# eeZee_big_tiny.net
KiCad netlist of a schematic drawn in EAGLE
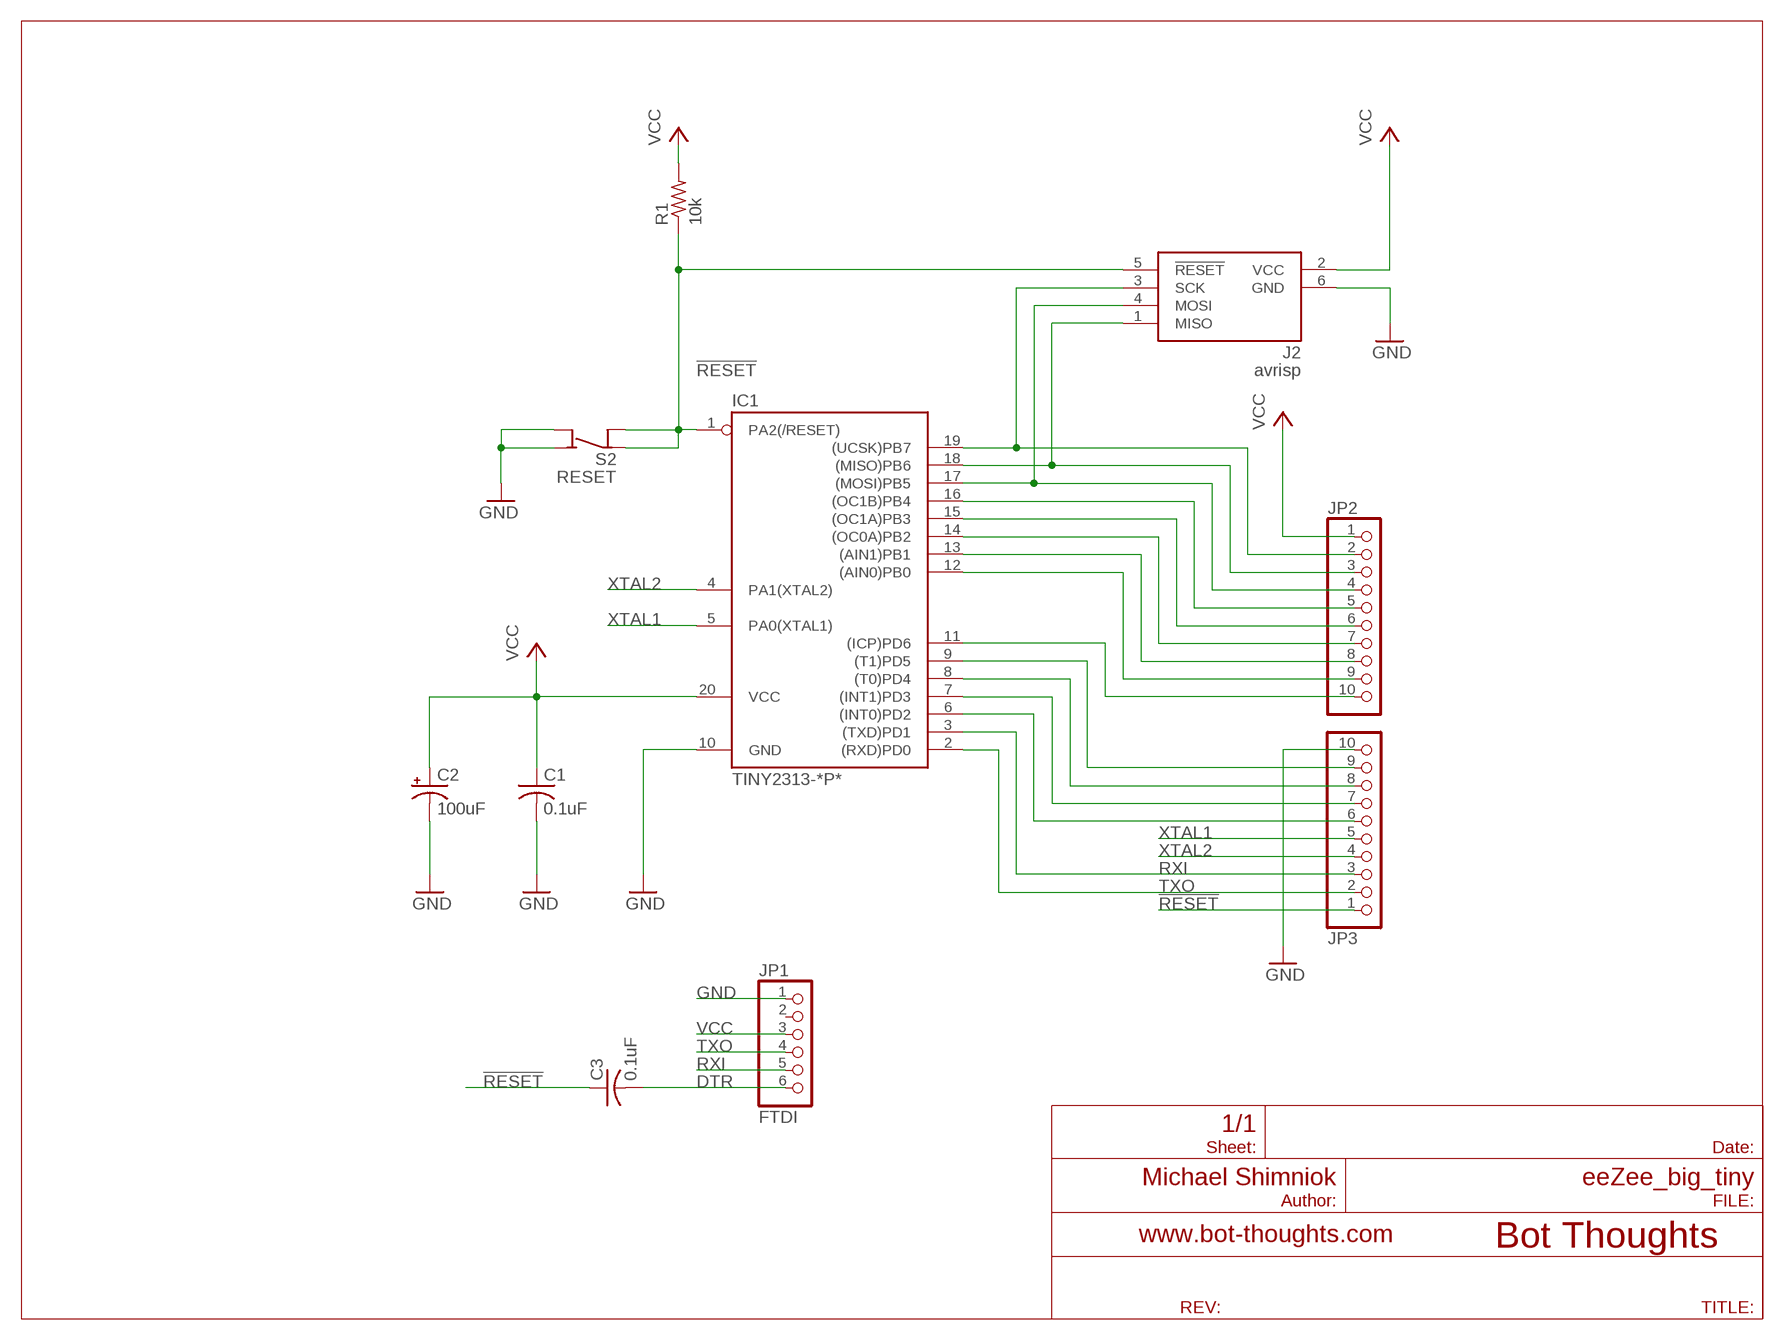
[diagram p0: schematic, sheet 1]

(export (version "E")
  (design (tool "Eeschema 10.0.6"))
  (components
    (comp (ref "C1")
      (value "0.1uF")
      (footprint "eagle-import:C0603")
      (fields (field (name "PARTNO") "0603YC104KAT2A"))
      (libsource (lib "eagle-import") (part "C-USC0603"))
    )
    (comp (ref "C2")
      (value "100uF")
      (footprint "eagle-import:SMC_B")
      (fields (field (name "PARTNO") "MCTT21X106M6R3CT"))
      (libsource (lib "eagle-import") (part "CPOL-USSMCB"))
    )
    (comp (ref "C3")
      (value "0.1uF")
      (footprint "eagle-import:C0603")
      (fields (field (name "PARTNO") "0603YC104KAT2A"))
      (libsource (lib "eagle-import") (part "C-USC0603"))
    )
    (comp (ref "IC1")
      (value "TINY2313-*P*")
      (footprint "eagle-import:DIL20")
      (libsource (lib "eagle-import") (part "TINY2313-P"))
    )
    (comp (ref "J2")
      (value "avrisp")
      (footprint "eagle-import:CON6P2R")
      (libsource (lib "eagle-import") (part "AVRISP6"))
    )
    (comp (ref "JP1")
      (value "FTDI")
      (footprint "eagle-import:1X06-S")
      (libsource (lib "eagle-import") (part "PINHD-1X06_2.54-S"))
    )
    (comp (ref "JP2")
      (value "PINHD-1X10_2.54-S")
      (footprint "eagle-import:1X10-S")
      (libsource (lib "eagle-import") (part "PINHD-1X10_2.54-S"))
    )
    (comp (ref "JP3")
      (value "PINHD-1X10_2.54-S")
      (footprint "eagle-import:1X10-S")
      (libsource (lib "eagle-import") (part "PINHD-1X10_2.54-S"))
    )
    (comp (ref "R1")
      (value "10k")
      (footprint "eagle-import:R0603")
      (fields (field (name "PARTNO") "ERJ-3GEYJ103V"))
      (libsource (lib "eagle-import") (part "R-US_R0603"))
    )
    (comp (ref "S2")
      (value "RESET")
      (footprint "eagle-import:6MMTACTILE_4PIN")
      (libsource (lib "eagle-import") (part "SPST4"))
    )
  )
  (nets
    (net (code "1") (name "/DTR") (class "Default")
      (node (ref "C3") (pin "2") (pinfunction "2_2") (pintype "passive"))
      (node (ref "JP1") (pin "6") (pinfunction "6_6") (pintype "passive"))
    )
    (net (code "2") (name "/RXI") (class "Default")
      (node (ref "IC1") (pin "3") (pinfunction "(TXD)PD1_3") (pintype "bidirectional"))
      (node (ref "JP1") (pin "5") (pinfunction "5_5") (pintype "passive"))
      (node (ref "JP3") (pin "3") (pinfunction "3_3") (pintype "passive"))
    )
    (net (code "3") (name "/TXO") (class "Default")
      (node (ref "IC1") (pin "2") (pinfunction "(RXD)PD0_2") (pintype "bidirectional"))
      (node (ref "JP1") (pin "4") (pinfunction "4_4") (pintype "passive"))
      (node (ref "JP3") (pin "2") (pinfunction "2_2") (pintype "passive"))
    )
    (net (code "4") (name "/XTAL1") (class "Default")
      (node (ref "IC1") (pin "5") (pinfunction "PA0(XTAL1)_5") (pintype "bidirectional"))
      (node (ref "JP3") (pin "5") (pinfunction "5_5") (pintype "passive"))
    )
    (net (code "5") (name "/XTAL2") (class "Default")
      (node (ref "IC1") (pin "4") (pinfunction "PA1(XTAL2)_4") (pintype "bidirectional"))
      (node (ref "JP3") (pin "4") (pinfunction "4_4") (pintype "passive"))
    )
    (net (code "6") (name "/~{RESET}") (class "Default")
      (node (ref "C3") (pin "1") (pinfunction "1_1") (pintype "passive"))
      (node (ref "IC1") (pin "1") (pinfunction "PA2(/RESET)_1") (pintype "input"))
      (node (ref "J2") (pin "5") (pinfunction "~{RESET}_5") (pintype "output"))
      (node (ref "JP3") (pin "1") (pinfunction "1_1") (pintype "passive"))
      (node (ref "R1") (pin "1") (pinfunction "1_1") (pintype "passive"))
      (node (ref "S2") (pin "B1") (pinfunction "COM_B1") (pintype "passive"))
      (node (ref "S2") (pin "B2") (pinfunction "COM_B2") (pintype "passive"))
    )
    (net (code "7") (name "GND") (class "Default")
      (node (ref "C1") (pin "2") (pinfunction "2_2") (pintype "passive"))
      (node (ref "C2") (pin "-") (pinfunction "-_-") (pintype "passive"))
      (node (ref "IC1") (pin "10") (pinfunction "GND_10") (pintype "power_in"))
      (node (ref "J2") (pin "6") (pinfunction "GND_6") (pintype "power_in"))
      (node (ref "JP1") (pin "1") (pinfunction "1_1") (pintype "passive"))
      (node (ref "JP3") (pin "10") (pinfunction "10_10") (pintype "passive"))
      (node (ref "S2") (pin "A1") (pinfunction "NO_A1") (pintype "passive"))
      (node (ref "S2") (pin "A2") (pinfunction "NO_A2") (pintype "passive"))
    )
    (net (code "8") (name "Net-(IC1-(AIN0)PB0)") (class "Default")
      (node (ref "IC1") (pin "12") (pinfunction "(AIN0)PB0_12") (pintype "bidirectional"))
      (node (ref "JP2") (pin "9") (pinfunction "9_9") (pintype "passive"))
    )
    (net (code "9") (name "Net-(IC1-(AIN1)PB1)") (class "Default")
      (node (ref "IC1") (pin "13") (pinfunction "(AIN1)PB1_13") (pintype "bidirectional"))
      (node (ref "JP2") (pin "8") (pinfunction "8_8") (pintype "passive"))
    )
    (net (code "10") (name "Net-(IC1-(ICP)PD6)") (class "Default")
      (node (ref "IC1") (pin "11") (pinfunction "(ICP)PD6_11") (pintype "bidirectional"))
      (node (ref "JP2") (pin "10") (pinfunction "10_10") (pintype "passive"))
    )
    (net (code "11") (name "Net-(IC1-(INT0)PD2)") (class "Default")
      (node (ref "IC1") (pin "6") (pinfunction "(INT0)PD2_6") (pintype "bidirectional"))
      (node (ref "JP3") (pin "6") (pinfunction "6_6") (pintype "passive"))
    )
    (net (code "12") (name "Net-(IC1-(INT1)PD3)") (class "Default")
      (node (ref "IC1") (pin "7") (pinfunction "(INT1)PD3_7") (pintype "bidirectional"))
      (node (ref "JP3") (pin "7") (pinfunction "7_7") (pintype "passive"))
    )
    (net (code "13") (name "Net-(IC1-(MISO)PB6)") (class "Default")
      (node (ref "IC1") (pin "18") (pinfunction "(MISO)PB6_18") (pintype "bidirectional"))
      (node (ref "J2") (pin "1") (pinfunction "MISO_1") (pintype "input"))
      (node (ref "JP2") (pin "3") (pinfunction "3_3") (pintype "passive"))
    )
    (net (code "14") (name "Net-(IC1-(MOSI)PB5)") (class "Default")
      (node (ref "IC1") (pin "17") (pinfunction "(MOSI)PB5_17") (pintype "bidirectional"))
      (node (ref "J2") (pin "4") (pinfunction "MOSI_4") (pintype "output"))
      (node (ref "JP2") (pin "4") (pinfunction "4_4") (pintype "passive"))
    )
    (net (code "15") (name "Net-(IC1-(OC0A)PB2)") (class "Default")
      (node (ref "IC1") (pin "14") (pinfunction "(OC0A)PB2_14") (pintype "bidirectional"))
      (node (ref "JP2") (pin "7") (pinfunction "7_7") (pintype "passive"))
    )
    (net (code "16") (name "Net-(IC1-(OC1A)PB3)") (class "Default")
      (node (ref "IC1") (pin "15") (pinfunction "(OC1A)PB3_15") (pintype "bidirectional"))
      (node (ref "JP2") (pin "6") (pinfunction "6_6") (pintype "passive"))
    )
    (net (code "17") (name "Net-(IC1-(OC1B)PB4)") (class "Default")
      (node (ref "IC1") (pin "16") (pinfunction "(OC1B)PB4_16") (pintype "bidirectional"))
      (node (ref "JP2") (pin "5") (pinfunction "5_5") (pintype "passive"))
    )
    (net (code "18") (name "Net-(IC1-(T0)PD4)") (class "Default")
      (node (ref "IC1") (pin "8") (pinfunction "(T0)PD4_8") (pintype "bidirectional"))
      (node (ref "JP3") (pin "8") (pinfunction "8_8") (pintype "passive"))
    )
    (net (code "19") (name "Net-(IC1-(T1)PD5)") (class "Default")
      (node (ref "IC1") (pin "9") (pinfunction "(T1)PD5_9") (pintype "bidirectional"))
      (node (ref "JP3") (pin "9") (pinfunction "9_9") (pintype "passive"))
    )
    (net (code "20") (name "Net-(IC1-(UCSK)PB7)") (class "Default")
      (node (ref "IC1") (pin "19") (pinfunction "(UCSK)PB7_19") (pintype "bidirectional"))
      (node (ref "J2") (pin "3") (pinfunction "SCK_3") (pintype "output"))
      (node (ref "JP2") (pin "2") (pinfunction "2_2") (pintype "passive"))
    )
    (net (code "21") (name "VCC") (class "Default")
      (node (ref "C1") (pin "1") (pinfunction "1_1") (pintype "passive"))
      (node (ref "C2") (pin "+") (pinfunction "+_+") (pintype "passive"))
      (node (ref "IC1") (pin "20") (pinfunction "VCC_20") (pintype "power_in"))
      (node (ref "J2") (pin "2") (pinfunction "VCC_2") (pintype "power_in"))
      (node (ref "JP1") (pin "3") (pinfunction "3_3") (pintype "passive"))
      (node (ref "JP2") (pin "1") (pinfunction "1_1") (pintype "passive"))
      (node (ref "R1") (pin "2") (pinfunction "2_2") (pintype "passive"))
    )
    (net (code "22") (name "unconnected-(JP1-Pad2)") (class "Default")
      (node (ref "JP1") (pin "2") (pinfunction "2_2") (pintype "passive"))
    )
  )
)
